# PRO30.net
KiCad netlist of a schematic drawn in EAGLE
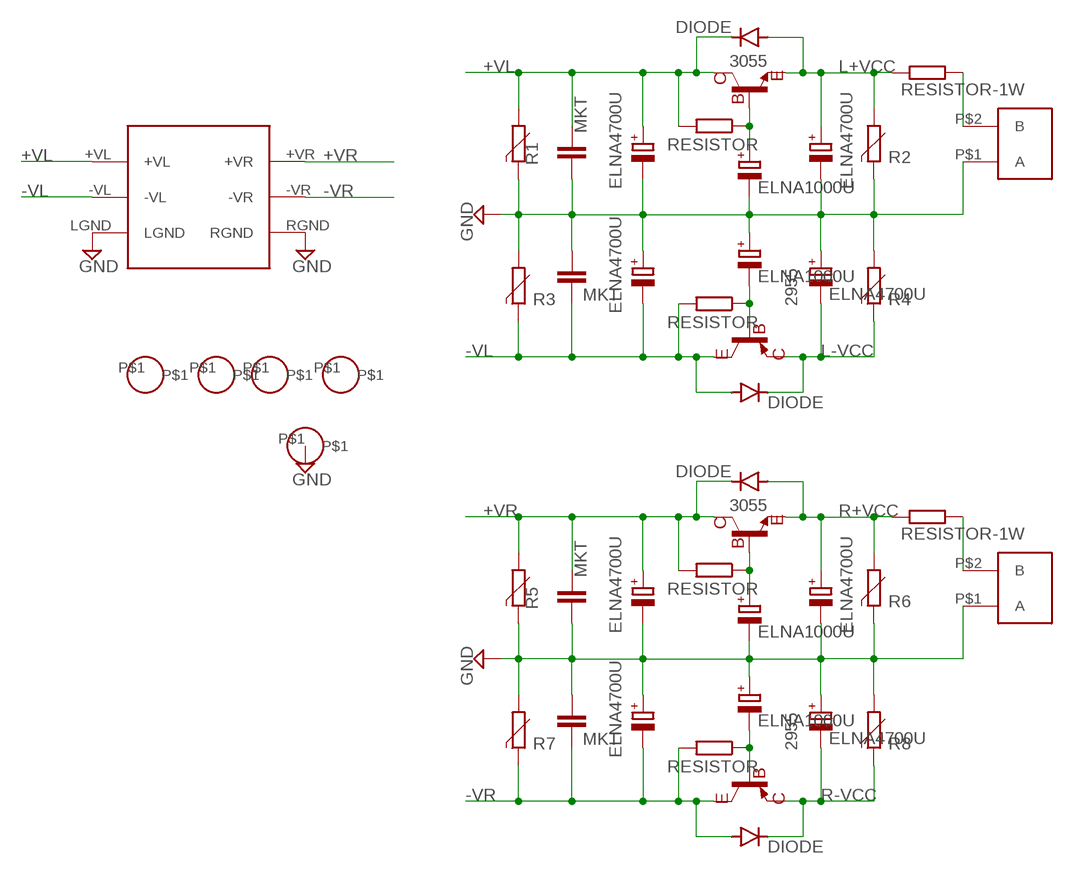
[diagram p0: schematic, sheet 1]
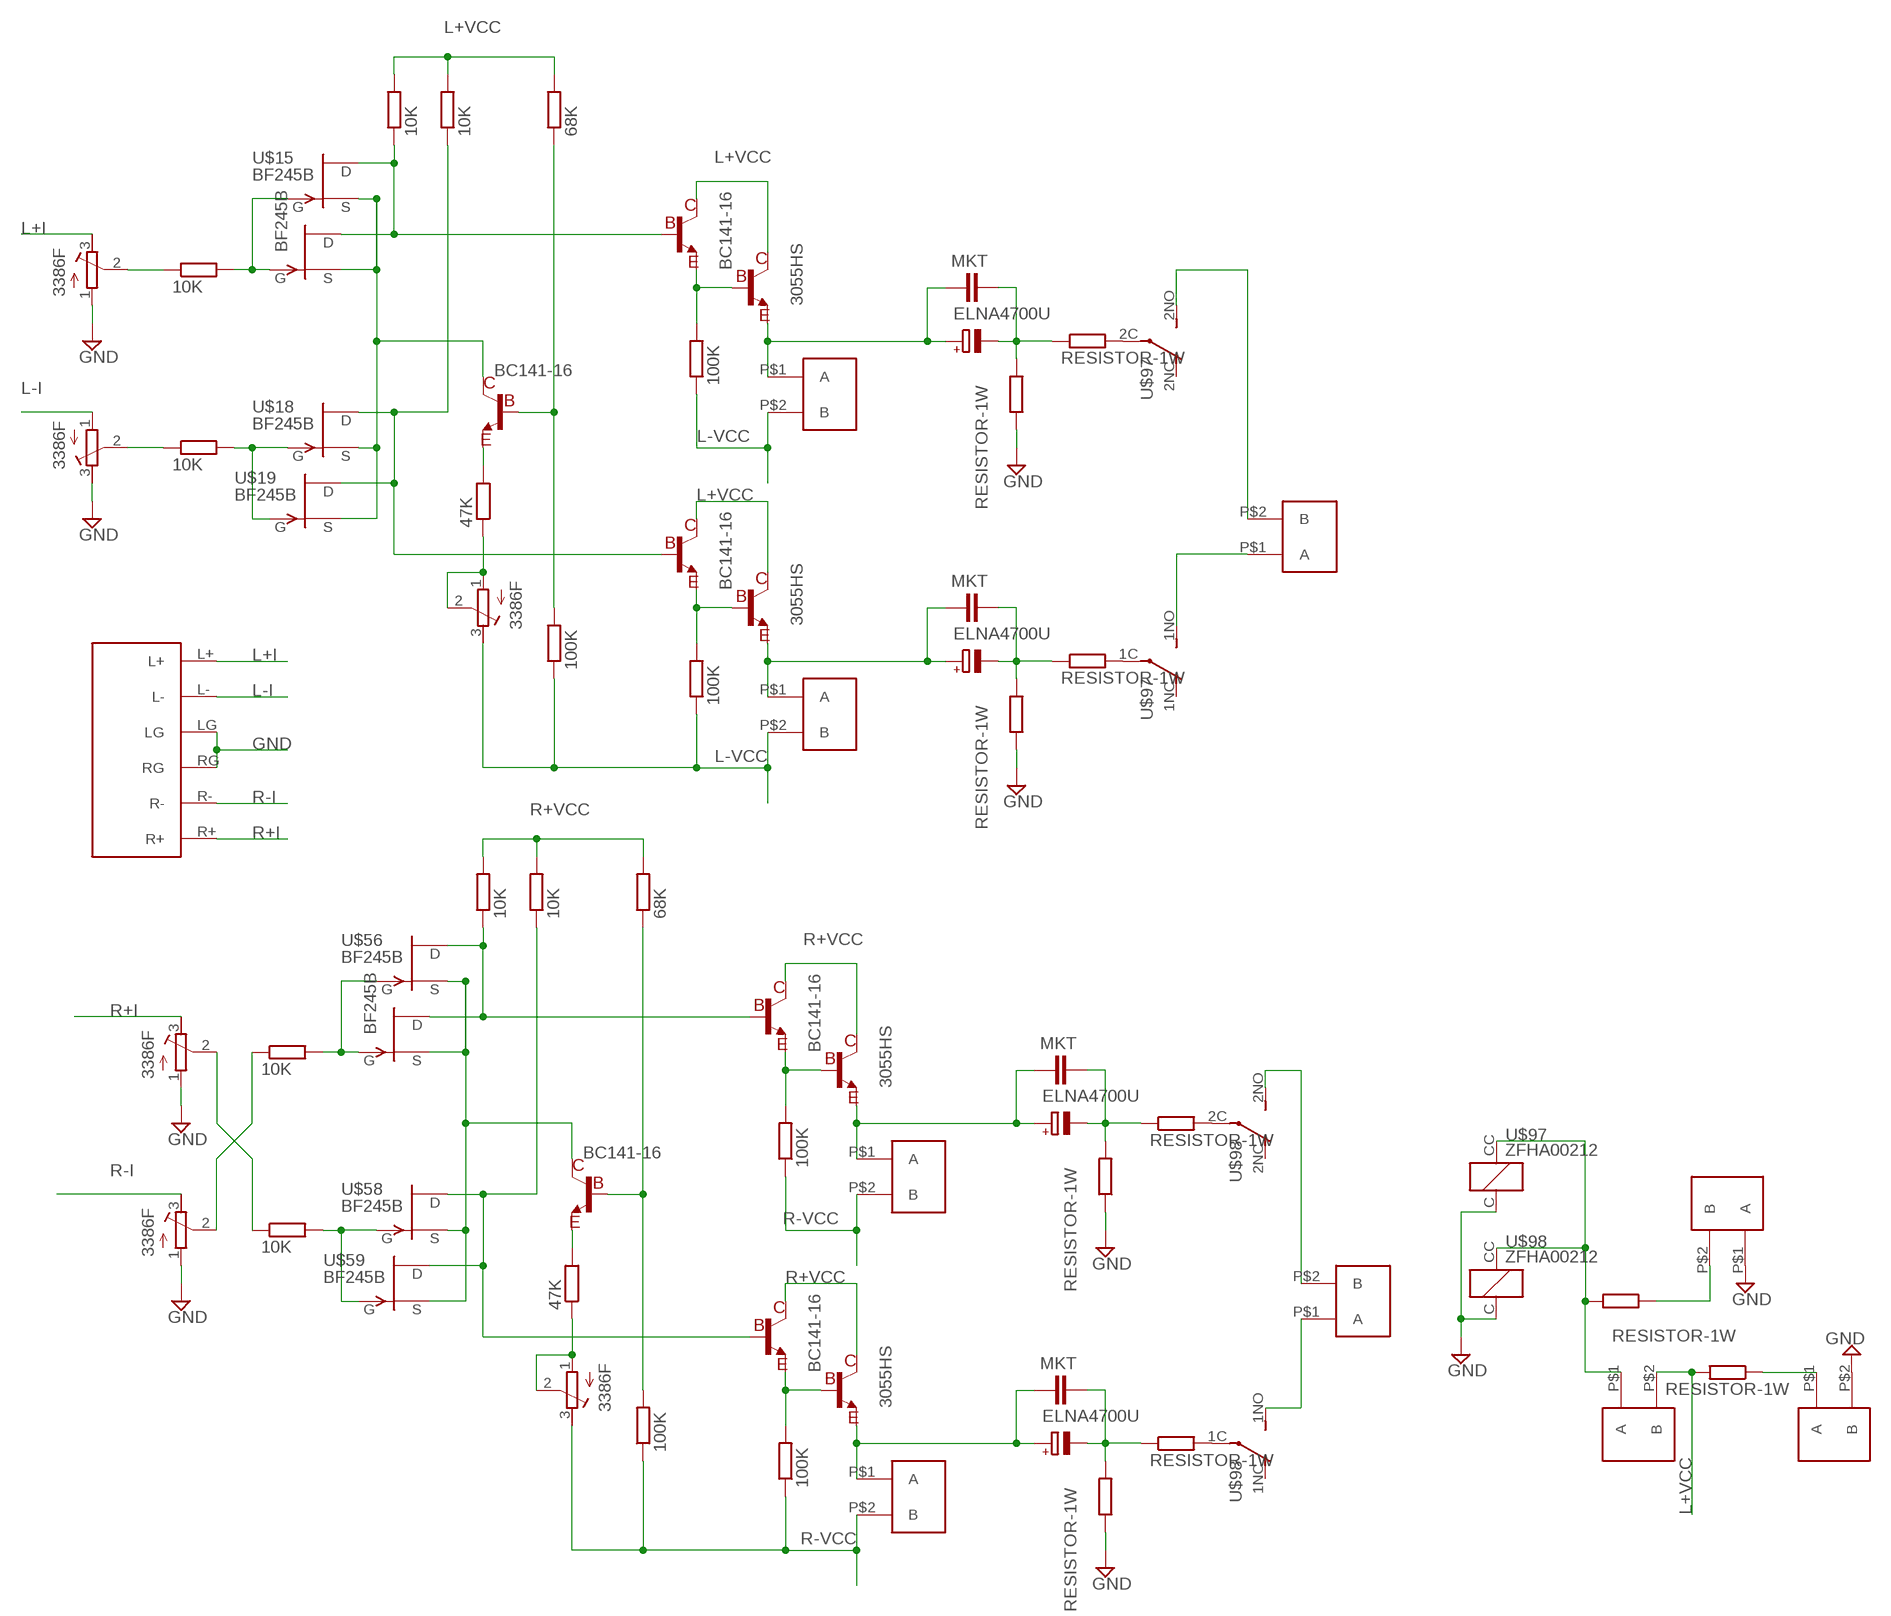
[diagram p1: schematic, sheet 2]

(export (version "E")
  (design (tool "Eeschema 10.0.6"))
  (components
    (comp (ref "DN>L")
      (value "OUT2")
      (footprint "eagle-import:OUT2_")
      (libsource (lib "eagle-import") (part "OUT2"))
    )
    (comp (ref "DP_SW")
      (value "OUT2")
      (footprint "eagle-import:OUT2_")
      (libsource (lib "eagle-import") (part "OUT2"))
    )
    (comp (ref "U$2")
      (value "AUDIO_INPUT")
      (footprint "eagle-import:AUDIO_INPUT")
      (libsource (lib "eagle-import") (part "AUDIO_INPUT"))
    )
    (comp (ref "U$4")
      (value "3386F")
      (footprint "eagle-import:3386")
      (libsource (lib "eagle-import") (part "3386F"))
    )
    (comp (ref "U$8")
      (value "3386F")
      (footprint "eagle-import:3386")
      (libsource (lib "eagle-import") (part "3386F"))
    )
    (comp (ref "U$11")
      (value "10K")
      (footprint "eagle-import:RESISTOR")
      (libsource (lib "eagle-import") (part "RESISTOR"))
    )
    (comp (ref "U$13")
      (value "68K")
      (footprint "eagle-import:RESISTOR")
      (libsource (lib "eagle-import") (part "RESISTOR"))
    )
    (comp (ref "U$14")
      (value "BC141-16")
      (footprint "eagle-import:TO39")
      (libsource (lib "eagle-import") (part "BC141-16"))
    )
    (comp (ref "U$15")
      (value "BF245B")
      (footprint "eagle-import:TO39")
      (libsource (lib "eagle-import") (part "BF245B"))
    )
    (comp (ref "U$17")
      (value "BF245B")
      (footprint "eagle-import:TO39")
      (libsource (lib "eagle-import") (part "BF245B"))
    )
    (comp (ref "U$18")
      (value "BF245B")
      (footprint "eagle-import:TO39")
      (libsource (lib "eagle-import") (part "BF245B"))
    )
    (comp (ref "U$19")
      (value "BF245B")
      (footprint "eagle-import:TO39")
      (libsource (lib "eagle-import") (part "BF245B"))
    )
    (comp (ref "U$20")
      (value "10K")
      (footprint "eagle-import:RESISTOR")
      (libsource (lib "eagle-import") (part "RESISTOR"))
    )
    (comp (ref "U$21")
      (value "10K")
      (footprint "eagle-import:RESISTOR")
      (libsource (lib "eagle-import") (part "RESISTOR"))
    )
    (comp (ref "U$22")
      (value "BC141-16")
      (footprint "eagle-import:TO39")
      (libsource (lib "eagle-import") (part "BC141-16"))
    )
    (comp (ref "U$23")
      (value "BC141-16")
      (footprint "eagle-import:TO39")
      (libsource (lib "eagle-import") (part "BC141-16"))
    )
    (comp (ref "U$25")
      (value "10K")
      (footprint "eagle-import:RESISTOR")
      (libsource (lib "eagle-import") (part "RESISTOR"))
    )
    (comp (ref "U$27")
      (value "47K")
      (footprint "eagle-import:RESISTOR")
      (libsource (lib "eagle-import") (part "RESISTOR"))
    )
    (comp (ref "U$31")
      (value "3386F")
      (footprint "eagle-import:3386")
      (libsource (lib "eagle-import") (part "3386F"))
    )
    (comp (ref "U$32")
      (value "3055HS")
      (footprint "eagle-import:POWER_TRANS_WHS")
      (libsource (lib "eagle-import") (part "3055HS"))
    )
    (comp (ref "U$33")
      (value "3055HS")
      (footprint "eagle-import:POWER_TRANS_WHS")
      (libsource (lib "eagle-import") (part "3055HS"))
    )
    (comp (ref "U$35")
      (value "OUT3")
      (footprint "eagle-import:OUT3_")
      (libsource (lib "eagle-import") (part "OUT3"))
    )
    (comp (ref "U$36")
      (value "ELNA4700U")
      (footprint "eagle-import:4700U")
      (libsource (lib "eagle-import") (part "ELNA4700U"))
    )
    (comp (ref "U$37")
      (value "MKT")
      (footprint "eagle-import:NTC")
      (libsource (lib "eagle-import") (part "MKT"))
    )
    (comp (ref "U$38")
      (value "RESISTOR-1W")
      (footprint "eagle-import:RESISTOR-1W")
      (libsource (lib "eagle-import") (part "RESISTOR-1W"))
    )
    (comp (ref "U$39")
      (value "RESISTOR-1W")
      (footprint "eagle-import:RESISTOR-1W")
      (libsource (lib "eagle-import") (part "RESISTOR-1W"))
    )
    (comp (ref "U$44")
      (value "OUT3")
      (footprint "eagle-import:OUT3_")
      (libsource (lib "eagle-import") (part "OUT3"))
    )
    (comp (ref "U$45")
      (value "ELNA4700U")
      (footprint "eagle-import:4700U")
      (libsource (lib "eagle-import") (part "ELNA4700U"))
    )
    (comp (ref "U$46")
      (value "MKT")
      (footprint "eagle-import:NTC")
      (libsource (lib "eagle-import") (part "MKT"))
    )
    (comp (ref "U$47")
      (value "RESISTOR-1W")
      (footprint "eagle-import:RESISTOR-1W")
      (libsource (lib "eagle-import") (part "RESISTOR-1W"))
    )
    (comp (ref "U$48")
      (value "RESISTOR-1W")
      (footprint "eagle-import:RESISTOR-1W")
      (libsource (lib "eagle-import") (part "RESISTOR-1W"))
    )
    (comp (ref "U$49")
      (value "100K")
      (footprint "eagle-import:RESISTOR")
      (libsource (lib "eagle-import") (part "RESISTOR"))
    )
    (comp (ref "U$50")
      (value "100K")
      (footprint "eagle-import:RESISTOR")
      (libsource (lib "eagle-import") (part "RESISTOR"))
    )
    (comp (ref "U$51")
      (value "100K")
      (footprint "eagle-import:RESISTOR")
      (libsource (lib "eagle-import") (part "RESISTOR"))
    )
    (comp (ref "U$52")
      (value "3386F")
      (footprint "eagle-import:3386")
      (libsource (lib "eagle-import") (part "3386F"))
    )
    (comp (ref "U$53")
      (value "3386F")
      (footprint "eagle-import:3386")
      (libsource (lib "eagle-import") (part "3386F"))
    )
    (comp (ref "U$54")
      (value "10K")
      (footprint "eagle-import:RESISTOR")
      (libsource (lib "eagle-import") (part "RESISTOR"))
    )
    (comp (ref "U$55")
      (value "BC141-16")
      (footprint "eagle-import:TO39")
      (libsource (lib "eagle-import") (part "BC141-16"))
    )
    (comp (ref "U$56")
      (value "BF245B")
      (footprint "eagle-import:TO39")
      (libsource (lib "eagle-import") (part "BF245B"))
    )
    (comp (ref "U$57")
      (value "BF245B")
      (footprint "eagle-import:TO39")
      (libsource (lib "eagle-import") (part "BF245B"))
    )
    (comp (ref "U$58")
      (value "BF245B")
      (footprint "eagle-import:TO39")
      (libsource (lib "eagle-import") (part "BF245B"))
    )
    (comp (ref "U$59")
      (value "BF245B")
      (footprint "eagle-import:TO39")
      (libsource (lib "eagle-import") (part "BF245B"))
    )
    (comp (ref "U$60")
      (value "10K")
      (footprint "eagle-import:RESISTOR")
      (libsource (lib "eagle-import") (part "RESISTOR"))
    )
    (comp (ref "U$61")
      (value "BC141-16")
      (footprint "eagle-import:TO39")
      (libsource (lib "eagle-import") (part "BC141-16"))
    )
    (comp (ref "U$62")
      (value "47K")
      (footprint "eagle-import:RESISTOR")
      (libsource (lib "eagle-import") (part "RESISTOR"))
    )
    (comp (ref "U$63")
      (value "3386F")
      (footprint "eagle-import:3386")
      (libsource (lib "eagle-import") (part "3386F"))
    )
    (comp (ref "U$64")
      (value "3055HS")
      (footprint "eagle-import:POWER_TRANS_WHS")
      (libsource (lib "eagle-import") (part "3055HS"))
    )
    (comp (ref "U$65")
      (value "OUT3")
      (footprint "eagle-import:OUT3_")
      (libsource (lib "eagle-import") (part "OUT3"))
    )
    (comp (ref "U$66")
      (value "ELNA4700U")
      (footprint "eagle-import:4700U")
      (libsource (lib "eagle-import") (part "ELNA4700U"))
    )
    (comp (ref "U$67")
      (value "MKT")
      (footprint "eagle-import:NTC")
      (libsource (lib "eagle-import") (part "MKT"))
    )
    (comp (ref "U$68")
      (value "RESISTOR-1W")
      (footprint "eagle-import:RESISTOR-1W")
      (libsource (lib "eagle-import") (part "RESISTOR-1W"))
    )
    (comp (ref "U$69")
      (value "RESISTOR-1W")
      (footprint "eagle-import:RESISTOR-1W")
      (libsource (lib "eagle-import") (part "RESISTOR-1W"))
    )
    (comp (ref "U$70")
      (value "BC141-16")
      (footprint "eagle-import:TO39")
      (libsource (lib "eagle-import") (part "BC141-16"))
    )
    (comp (ref "U$71")
      (value "3055HS")
      (footprint "eagle-import:POWER_TRANS_WHS")
      (libsource (lib "eagle-import") (part "3055HS"))
    )
    (comp (ref "U$72")
      (value "OUT3")
      (footprint "eagle-import:OUT3_")
      (libsource (lib "eagle-import") (part "OUT3"))
    )
    (comp (ref "U$73")
      (value "ELNA4700U")
      (footprint "eagle-import:4700U")
      (libsource (lib "eagle-import") (part "ELNA4700U"))
    )
    (comp (ref "U$74")
      (value "MKT")
      (footprint "eagle-import:NTC")
      (libsource (lib "eagle-import") (part "MKT"))
    )
    (comp (ref "U$75")
      (value "RESISTOR-1W")
      (footprint "eagle-import:RESISTOR-1W")
      (libsource (lib "eagle-import") (part "RESISTOR-1W"))
    )
    (comp (ref "U$76")
      (value "RESISTOR-1W")
      (footprint "eagle-import:RESISTOR-1W")
      (libsource (lib "eagle-import") (part "RESISTOR-1W"))
    )
    (comp (ref "U$77")
      (value "100K")
      (footprint "eagle-import:RESISTOR")
      (libsource (lib "eagle-import") (part "RESISTOR"))
    )
    (comp (ref "U$78")
      (value "100K")
      (footprint "eagle-import:RESISTOR")
      (libsource (lib "eagle-import") (part "RESISTOR"))
    )
    (comp (ref "U$79")
      (value "100K")
      (footprint "eagle-import:RESISTOR")
      (libsource (lib "eagle-import") (part "RESISTOR"))
    )
    (comp (ref "U$80")
      (value "68K")
      (footprint "eagle-import:RESISTOR")
      (libsource (lib "eagle-import") (part "RESISTOR"))
    )
    (comp (ref "U$81")
      (value "10K")
      (footprint "eagle-import:RESISTOR")
      (libsource (lib "eagle-import") (part "RESISTOR"))
    )
    (comp (ref "U$82")
      (value "10K")
      (footprint "eagle-import:RESISTOR")
      (libsource (lib "eagle-import") (part "RESISTOR"))
    )
    (comp (ref "U$97")
      (value "ZFHA00212")
      (footprint "eagle-import:ZFHA002")
      (libsource (lib "eagle-import") (part "ZFHA00212"))
    )
    (comp (ref "U$98")
      (value "ZFHA00212")
      (footprint "eagle-import:ZFHA002")
      (libsource (lib "eagle-import") (part "ZFHA00212"))
    )
    (comp (ref "U$99")
      (value "RESISTOR-1W")
      (footprint "eagle-import:RESISTOR-1W")
      (libsource (lib "eagle-import") (part "RESISTOR-1W"))
    )
    (comp (ref "U$100")
      (value "RESISTOR-1W")
      (footprint "eagle-import:RESISTOR-1W")
      (libsource (lib "eagle-import") (part "RESISTOR-1W"))
    )
    (comp (ref "U$103")
      (value "OUT2")
      (footprint "eagle-import:OUT2_")
      (libsource (lib "eagle-import") (part "OUT2"))
    )
    (comp (ref "U$104")
      (value "OUT3")
      (footprint "eagle-import:OUT3_")
      (libsource (lib "eagle-import") (part "OUT3"))
    )
    (comp (ref "U$105")
      (value "OUT3")
      (footprint "eagle-import:OUT3_")
      (libsource (lib "eagle-import") (part "OUT3"))
    )
    (comp (ref "R1")
      (value "NTC")
      (footprint "eagle-import:NTC")
      (libsource (lib "eagle-import") (part "NTC"))
    )
    (comp (ref "R2")
      (value "NTC")
      (footprint "eagle-import:NTC")
      (libsource (lib "eagle-import") (part "NTC"))
    )
    (comp (ref "R3")
      (value "NTC")
      (footprint "eagle-import:NTC")
      (libsource (lib "eagle-import") (part "NTC"))
    )
    (comp (ref "R4")
      (value "NTC")
      (footprint "eagle-import:NTC")
      (libsource (lib "eagle-import") (part "NTC"))
    )
    (comp (ref "R5")
      (value "NTC")
      (footprint "eagle-import:NTC")
      (libsource (lib "eagle-import") (part "NTC"))
    )
    (comp (ref "R6")
      (value "NTC")
      (footprint "eagle-import:NTC")
      (libsource (lib "eagle-import") (part "NTC"))
    )
    (comp (ref "R7")
      (value "NTC")
      (footprint "eagle-import:NTC")
      (libsource (lib "eagle-import") (part "NTC"))
    )
    (comp (ref "R8")
      (value "NTC")
      (footprint "eagle-import:NTC")
      (libsource (lib "eagle-import") (part "NTC"))
    )
    (comp (ref "U$1")
      (value "INPUT")
      (footprint "eagle-import:INPUT")
      (libsource (lib "eagle-import") (part "INPUT"))
    )
    (comp (ref "U$3")
      (value "ELNA4700U")
      (footprint "eagle-import:4700U")
      (libsource (lib "eagle-import") (part "ELNA4700U"))
    )
    (comp (ref "U$5")
      (value "ELNA4700U")
      (footprint "eagle-import:4700U")
      (libsource (lib "eagle-import") (part "ELNA4700U"))
    )
    (comp (ref "U$6")
      (value "ELNA4700U")
      (footprint "eagle-import:4700U")
      (libsource (lib "eagle-import") (part "ELNA4700U"))
    )
    (comp (ref "U$7")
      (value "ELNA4700U")
      (footprint "eagle-import:4700U")
      (libsource (lib "eagle-import") (part "ELNA4700U"))
    )
    (comp (ref "U$9")
      (value "ELNA4700U")
      (footprint "eagle-import:4700U")
      (libsource (lib "eagle-import") (part "ELNA4700U"))
    )
    (comp (ref "U$10")
      (value "ELNA4700U")
      (footprint "eagle-import:4700U")
      (libsource (lib "eagle-import") (part "ELNA4700U"))
    )
    (comp (ref "U$12")
      (value "ELNA1000U")
      (footprint "eagle-import:1000U")
      (libsource (lib "eagle-import") (part "ELNA1000U"))
    )
    (comp (ref "U$16")
      (value "ELNA1000U")
      (footprint "eagle-import:1000U")
      (libsource (lib "eagle-import") (part "ELNA1000U"))
    )
    (comp (ref "U$24")
      (value "2955")
      (footprint "eagle-import:POWER_TRANS")
      (libsource (lib "eagle-import") (part "2955"))
    )
    (comp (ref "U$26")
      (value "3055")
      (footprint "eagle-import:POWER_TRANS")
      (libsource (lib "eagle-import") (part "3055"))
    )
    (comp (ref "U$28")
      (value "DIODE")
      (footprint "eagle-import:DIODE")
      (libsource (lib "eagle-import") (part "DIODE"))
    )
    (comp (ref "U$29")
      (value "DIODE")
      (footprint "eagle-import:DIODE")
      (libsource (lib "eagle-import") (part "DIODE"))
    )
    (comp (ref "U$30")
      (value "MKT")
      (footprint "eagle-import:NTC")
      (libsource (lib "eagle-import") (part "MKT"))
    )
    (comp (ref "U$34")
      (value "MKT")
      (footprint "eagle-import:NTC")
      (libsource (lib "eagle-import") (part "MKT"))
    )
    (comp (ref "U$40")
      (value "RESISTOR")
      (footprint "eagle-import:RESISTOR")
      (libsource (lib "eagle-import") (part "RESISTOR"))
    )
    (comp (ref "U$41")
      (value "OUT2")
      (footprint "eagle-import:OUT2_")
      (libsource (lib "eagle-import") (part "OUT2"))
    )
    (comp (ref "U$42")
      (value "RESISTOR-1W")
      (footprint "eagle-import:RESISTOR-1W")
      (libsource (lib "eagle-import") (part "RESISTOR-1W"))
    )
    (comp (ref "U$43")
      (value "RESISTOR")
      (footprint "eagle-import:RESISTOR")
      (libsource (lib "eagle-import") (part "RESISTOR"))
    )
    (comp (ref "U$83")
      (value "ELNA4700U")
      (footprint "eagle-import:4700U")
      (libsource (lib "eagle-import") (part "ELNA4700U"))
    )
    (comp (ref "U$84")
      (value "ELNA4700U")
      (footprint "eagle-import:4700U")
      (libsource (lib "eagle-import") (part "ELNA4700U"))
    )
    (comp (ref "U$85")
      (value "ELNA1000U")
      (footprint "eagle-import:1000U")
      (libsource (lib "eagle-import") (part "ELNA1000U"))
    )
    (comp (ref "U$86")
      (value "ELNA1000U")
      (footprint "eagle-import:1000U")
      (libsource (lib "eagle-import") (part "ELNA1000U"))
    )
    (comp (ref "U$87")
      (value "2955")
      (footprint "eagle-import:POWER_TRANS")
      (libsource (lib "eagle-import") (part "2955"))
    )
    (comp (ref "U$88")
      (value "3055")
      (footprint "eagle-import:POWER_TRANS")
      (libsource (lib "eagle-import") (part "3055"))
    )
    (comp (ref "U$89")
      (value "DIODE")
      (footprint "eagle-import:DIODE")
      (libsource (lib "eagle-import") (part "DIODE"))
    )
    (comp (ref "U$90")
      (value "DIODE")
      (footprint "eagle-import:DIODE")
      (libsource (lib "eagle-import") (part "DIODE"))
    )
    (comp (ref "U$91")
      (value "MKT")
      (footprint "eagle-import:NTC")
      (libsource (lib "eagle-import") (part "MKT"))
    )
    (comp (ref "U$92")
      (value "MKT")
      (footprint "eagle-import:NTC")
      (libsource (lib "eagle-import") (part "MKT"))
    )
    (comp (ref "U$93")
      (value "RESISTOR")
      (footprint "eagle-import:RESISTOR")
      (libsource (lib "eagle-import") (part "RESISTOR"))
    )
    (comp (ref "U$94")
      (value "OUT2")
      (footprint "eagle-import:OUT2_")
      (libsource (lib "eagle-import") (part "OUT2"))
    )
    (comp (ref "U$95")
      (value "RESISTOR-1W")
      (footprint "eagle-import:RESISTOR-1W")
      (libsource (lib "eagle-import") (part "RESISTOR-1W"))
    )
    (comp (ref "U$96")
      (value "RESISTOR")
      (footprint "eagle-import:RESISTOR")
      (libsource (lib "eagle-import") (part "RESISTOR"))
    )
    (comp (ref "U$101")
      (value "HOLE")
      (footprint "eagle-import:HOLE")
      (libsource (lib "eagle-import") (part "HOLE"))
    )
    (comp (ref "U$102")
      (value "HOLE")
      (footprint "eagle-import:HOLE")
      (libsource (lib "eagle-import") (part "HOLE"))
    )
    (comp (ref "U$106")
      (value "HOLE")
      (footprint "eagle-import:HOLE")
      (libsource (lib "eagle-import") (part "HOLE"))
    )
    (comp (ref "U$107")
      (value "HOLE")
      (footprint "eagle-import:HOLE")
      (libsource (lib "eagle-import") (part "HOLE"))
    )
    (comp (ref "U$108")
      (value "HOLE")
      (footprint "eagle-import:HOLE")
      (libsource (lib "eagle-import") (part "HOLE"))
    )
  )
  (nets
    (net (code "1") (name "+VL") (class "Default")
      (node (ref "R1") (pin "2") (pinfunction "2_2") (pintype "passive"))
      (node (ref "U$1") (pin "+VL") (pinfunction "+VL_+VL") (pintype "bidirectional"))
      (node (ref "U$26") (pin "C") (pinfunction "C_C") (pintype "passive"))
      (node (ref "U$28") (pin "C") (pinfunction "C_C") (pintype "passive"))
      (node (ref "U$3") (pin "+") (pinfunction "+_+") (pintype "passive"))
      (node (ref "U$30") (pin "1") (pinfunction "1_1") (pintype "passive"))
      (node (ref "U$40") (pin "P$2") (pinfunction "2_P$2") (pintype "passive"))
    )
    (net (code "2") (name "+VR") (class "Default")
      (node (ref "R5") (pin "2") (pinfunction "2_2") (pintype "passive"))
      (node (ref "U$1") (pin "+VR") (pinfunction "+VR_+VR") (pintype "bidirectional"))
      (node (ref "U$88") (pin "C") (pinfunction "C_C") (pintype "passive"))
      (node (ref "U$89") (pin "C") (pinfunction "C_C") (pintype "passive"))
      (node (ref "U$9") (pin "+") (pinfunction "+_+") (pintype "passive"))
      (node (ref "U$91") (pin "1") (pinfunction "1_1") (pintype "passive"))
      (node (ref "U$93") (pin "P$2") (pinfunction "2_P$2") (pintype "passive"))
    )
    (net (code "3") (name "-VL") (class "Default")
      (node (ref "R3") (pin "1") (pinfunction "1_1") (pintype "passive"))
      (node (ref "U$1") (pin "-VL") (pinfunction "-VL_-VL") (pintype "bidirectional"))
      (node (ref "U$24") (pin "C") (pinfunction "C_C") (pintype "passive"))
      (node (ref "U$29") (pin "A") (pinfunction "A_A") (pintype "passive"))
      (node (ref "U$34") (pin "2") (pinfunction "2_2") (pintype "passive"))
      (node (ref "U$43") (pin "P$2") (pinfunction "2_P$2") (pintype "passive"))
      (node (ref "U$7") (pin "-") (pinfunction "-_-") (pintype "passive"))
    )
    (net (code "4") (name "-VR") (class "Default")
      (node (ref "R7") (pin "1") (pinfunction "1_1") (pintype "passive"))
      (node (ref "U$1") (pin "-VR") (pinfunction "-VR_-VR") (pintype "bidirectional"))
      (node (ref "U$84") (pin "-") (pinfunction "-_-") (pintype "passive"))
      (node (ref "U$87") (pin "C") (pinfunction "C_C") (pintype "passive"))
      (node (ref "U$90") (pin "A") (pinfunction "A_A") (pintype "passive"))
      (node (ref "U$92") (pin "2") (pinfunction "2_2") (pintype "passive"))
      (node (ref "U$96") (pin "P$2") (pinfunction "2_P$2") (pintype "passive"))
    )
    (net (code "5") (name "GND") (class "Default")
      (node (ref "DN>L") (pin "P$2") (pinfunction "B_P$2") (pintype "bidirectional"))
      (node (ref "R1") (pin "1") (pinfunction "1_1") (pintype "passive"))
      (node (ref "R2") (pin "1") (pinfunction "1_1") (pintype "passive"))
      (node (ref "R3") (pin "2") (pinfunction "2_2") (pintype "passive"))
      (node (ref "R4") (pin "2") (pinfunction "2_2") (pintype "passive"))
      (node (ref "R5") (pin "1") (pinfunction "1_1") (pintype "passive"))
      (node (ref "R6") (pin "1") (pinfunction "1_1") (pintype "passive"))
      (node (ref "R7") (pin "2") (pinfunction "2_2") (pintype "passive"))
      (node (ref "R8") (pin "2") (pinfunction "2_2") (pintype "passive"))
      (node (ref "U$1") (pin "LGND") (pinfunction "LGND_LGND") (pintype "bidirectional"))
      (node (ref "U$1") (pin "RGND") (pinfunction "RGND_RGND") (pintype "bidirectional"))
      (node (ref "U$10") (pin "+") (pinfunction "+_+") (pintype "passive"))
      (node (ref "U$103") (pin "P$1") (pinfunction "A_P$1") (pintype "bidirectional"))
      (node (ref "U$108") (pin "P$1") (pinfunction "P$1_P$1") (pintype "bidirectional"))
      (node (ref "U$12") (pin "-") (pinfunction "-_-") (pintype "passive"))
      (node (ref "U$16") (pin "+") (pinfunction "+_+") (pintype "passive"))
      (node (ref "U$2") (pin "LG") (pinfunction "LG_LG") (pintype "bidirectional"))
      (node (ref "U$2") (pin "RG") (pinfunction "RG_RG") (pintype "bidirectional"))
      (node (ref "U$3") (pin "-") (pinfunction "-_-") (pintype "passive"))
      (node (ref "U$30") (pin "2") (pinfunction "2_2") (pintype "passive"))
      (node (ref "U$34") (pin "1") (pinfunction "1_1") (pintype "passive"))
      (node (ref "U$38") (pin "P$1") (pinfunction "1_P$1") (pintype "passive"))
      (node (ref "U$4") (pin "1") (pinfunction "1_1") (pintype "passive"))
      (node (ref "U$41") (pin "P$1") (pinfunction "A_P$1") (pintype "bidirectional"))
      (node (ref "U$47") (pin "P$1") (pinfunction "1_P$1") (pintype "passive"))
      (node (ref "U$5") (pin "+") (pinfunction "+_+") (pintype "passive"))
      (node (ref "U$52") (pin "1") (pinfunction "1_1") (pintype "passive"))
      (node (ref "U$53") (pin "1") (pinfunction "1_1") (pintype "passive"))
      (node (ref "U$6") (pin "-") (pinfunction "-_-") (pintype "passive"))
      (node (ref "U$68") (pin "P$1") (pinfunction "1_P$1") (pintype "passive"))
      (node (ref "U$7") (pin "+") (pinfunction "+_+") (pintype "passive"))
      (node (ref "U$75") (pin "P$1") (pinfunction "1_P$1") (pintype "passive"))
      (node (ref "U$8") (pin "3") (pinfunction "3_3") (pintype "passive"))
      (node (ref "U$83") (pin "-") (pinfunction "-_-") (pintype "passive"))
      (node (ref "U$84") (pin "+") (pinfunction "+_+") (pintype "passive"))
      (node (ref "U$85") (pin "-") (pinfunction "-_-") (pintype "passive"))
      (node (ref "U$86") (pin "+") (pinfunction "+_+") (pintype "passive"))
      (node (ref "U$9") (pin "-") (pinfunction "-_-") (pintype "passive"))
      (node (ref "U$91") (pin "2") (pinfunction "2_2") (pintype "passive"))
      (node (ref "U$92") (pin "1") (pinfunction "1_1") (pintype "passive"))
      (node (ref "U$94") (pin "P$1") (pinfunction "A_P$1") (pintype "bidirectional"))
      (node (ref "U$97") (pin "C") (pinfunction "C_C") (pintype "passive"))
      (node (ref "U$98") (pin "C") (pinfunction "C_C") (pintype "passive"))
    )
    (net (code "6") (name "L+I") (class "Default")
      (node (ref "U$2") (pin "L+") (pinfunction "L+_L+") (pintype "bidirectional"))
      (node (ref "U$4") (pin "3") (pinfunction "3_3") (pintype "passive"))
    )
    (net (code "7") (name "L+VCC") (class "Default")
      (node (ref "DP_SW") (pin "P$2") (pinfunction "B_P$2") (pintype "bidirectional"))
      (node (ref "R2") (pin "2") (pinfunction "2_2") (pintype "passive"))
      (node (ref "U$13") (pin "P$2") (pinfunction "2_P$2") (pintype "passive"))
      (node (ref "U$20") (pin "P$2") (pinfunction "2_P$2") (pintype "passive"))
      (node (ref "U$22") (pin "C/G") (pinfunction "C_C/G") (pintype "passive"))
      (node (ref "U$23") (pin "C/G") (pinfunction "C_C/G") (pintype "passive"))
      (node (ref "U$25") (pin "P$2") (pinfunction "2_P$2") (pintype "passive"))
      (node (ref "U$26") (pin "E") (pinfunction "E_E") (pintype "passive"))
      (node (ref "U$28") (pin "A") (pinfunction "A_A") (pintype "passive"))
      (node (ref "U$32") (pin "C") (pinfunction "C_C") (pintype "passive"))
      (node (ref "U$33") (pin "C") (pinfunction "C_C") (pintype "passive"))
      (node (ref "U$42") (pin "P$1") (pinfunction "1_P$1") (pintype "passive"))
      (node (ref "U$6") (pin "+") (pinfunction "+_+") (pintype "passive"))
      (node (ref "U$99") (pin "P$2") (pinfunction "2_P$2") (pintype "passive"))
    )
    (net (code "8") (name "L-I") (class "Default")
      (node (ref "U$2") (pin "L-") (pinfunction "L-_L-") (pintype "bidirectional"))
      (node (ref "U$8") (pin "1") (pinfunction "1_1") (pintype "passive"))
    )
    (net (code "9") (name "L-VCC") (class "Default")
      (node (ref "R4") (pin "1") (pinfunction "1_1") (pintype "passive"))
      (node (ref "U$24") (pin "E") (pinfunction "E_E") (pintype "passive"))
      (node (ref "U$29") (pin "C") (pinfunction "C_C") (pintype "passive"))
      (node (ref "U$31") (pin "3") (pinfunction "3_3") (pintype "passive"))
      (node (ref "U$35") (pin "P$2") (pinfunction "B_P$2") (pintype "bidirectional"))
      (node (ref "U$44") (pin "P$2") (pinfunction "B_P$2") (pintype "bidirectional"))
      (node (ref "U$49") (pin "P$1") (pinfunction "1_P$1") (pintype "passive"))
      (node (ref "U$5") (pin "-") (pinfunction "-_-") (pintype "passive"))
      (node (ref "U$50") (pin "P$1") (pinfunction "1_P$1") (pintype "passive"))
      (node (ref "U$51") (pin "P$1") (pinfunction "1_P$1") (pintype "passive"))
    )
    (net (code "10") (name "Net-(DN>L-A)") (class "Default")
      (node (ref "DN>L") (pin "P$1") (pinfunction "A_P$1") (pintype "bidirectional"))
      (node (ref "U$99") (pin "P$1") (pinfunction "1_P$1") (pintype "passive"))
    )
    (net (code "11") (name "Net-(DP_SW-A)") (class "Default")
      (node (ref "DP_SW") (pin "P$1") (pinfunction "A_P$1") (pintype "bidirectional"))
      (node (ref "U$100") (pin "P$2") (pinfunction "2_P$2") (pintype "passive"))
      (node (ref "U$97") (pin "CC") (pinfunction "CT_CC") (pintype "passive"))
      (node (ref "U$98") (pin "CC") (pinfunction "CT_CC") (pintype "passive"))
    )
    (net (code "12") (name "Net-(U$11-1)") (class "Default")
      (node (ref "U$11") (pin "P$1") (pinfunction "1_P$1") (pintype "passive"))
      (node (ref "U$4") (pin "2") (pinfunction "2_2") (pintype "passive"))
    )
    (net (code "13") (name "Net-(U$11-2)") (class "Default")
      (node (ref "U$11") (pin "P$2") (pinfunction "2_P$2") (pintype "passive"))
      (node (ref "U$15") (pin "C/G") (pinfunction "G_C/G") (pintype "passive"))
      (node (ref "U$17") (pin "C/G") (pinfunction "G_C/G") (pintype "passive"))
    )
    (net (code "14") (name "Net-(U$13-1)") (class "Default")
      (node (ref "U$13") (pin "P$1") (pinfunction "1_P$1") (pintype "passive"))
      (node (ref "U$14") (pin "B/S") (pinfunction "B_B/S") (pintype "passive"))
      (node (ref "U$49") (pin "P$2") (pinfunction "2_P$2") (pintype "passive"))
    )
    (net (code "15") (name "Net-(U$14-C)") (class "Default")
      (node (ref "U$14") (pin "C/G") (pinfunction "C_C/G") (pintype "passive"))
      (node (ref "U$15") (pin "B/S") (pinfunction "S_B/S") (pintype "passive"))
      (node (ref "U$17") (pin "B/S") (pinfunction "S_B/S") (pintype "passive"))
      (node (ref "U$18") (pin "B/S") (pinfunction "S_B/S") (pintype "passive"))
      (node (ref "U$19") (pin "B/S") (pinfunction "S_B/S") (pintype "passive"))
    )
    (net (code "16") (name "Net-(U$14-E)") (class "Default")
      (node (ref "U$14") (pin "E/D") (pinfunction "E_E/D") (pintype "passive"))
      (node (ref "U$27") (pin "P$2") (pinfunction "2_P$2") (pintype "passive"))
    )
    (net (code "17") (name "Net-(U$15-D)") (class "Default")
      (node (ref "U$15") (pin "E/D") (pinfunction "D_E/D") (pintype "passive"))
      (node (ref "U$17") (pin "E/D") (pinfunction "D_E/D") (pintype "passive"))
      (node (ref "U$22") (pin "B/S") (pinfunction "B_B/S") (pintype "passive"))
      (node (ref "U$25") (pin "P$1") (pinfunction "1_P$1") (pintype "passive"))
    )
    (net (code "18") (name "Net-(U$18-D)") (class "Default")
      (node (ref "U$18") (pin "E/D") (pinfunction "D_E/D") (pintype "passive"))
      (node (ref "U$19") (pin "E/D") (pinfunction "D_E/D") (pintype "passive"))
      (node (ref "U$20") (pin "P$1") (pinfunction "1_P$1") (pintype "passive"))
      (node (ref "U$23") (pin "B/S") (pinfunction "B_B/S") (pintype "passive"))
    )
    (net (code "19") (name "Net-(U$18-G)") (class "Default")
      (node (ref "U$18") (pin "C/G") (pinfunction "G_C/G") (pintype "passive"))
      (node (ref "U$19") (pin "C/G") (pinfunction "G_C/G") (pintype "passive"))
      (node (ref "U$21") (pin "P$2") (pinfunction "2_P$2") (pintype "passive"))
    )
    (net (code "20") (name "Net-(U$21-1)") (class "Default")
      (node (ref "U$21") (pin "P$1") (pinfunction "1_P$1") (pintype "passive"))
      (node (ref "U$8") (pin "2") (pinfunction "2_2") (pintype "passive"))
    )
    (net (code "21") (name "Net-(U$22-E)") (class "Default")
      (node (ref "U$22") (pin "E/D") (pinfunction "E_E/D") (pintype "passive"))
      (node (ref "U$33") (pin "B") (pinfunction "B_B") (pintype "passive"))
      (node (ref "U$51") (pin "P$2") (pinfunction "2_P$2") (pintype "passive"))
    )
    (net (code "22") (name "Net-(U$23-E)") (class "Default")
      (node (ref "U$23") (pin "E/D") (pinfunction "E_E/D") (pintype "passive"))
      (node (ref "U$32") (pin "B") (pinfunction "B_B") (pintype "passive"))
      (node (ref "U$50") (pin "P$2") (pinfunction "2_P$2") (pintype "passive"))
    )
    (net (code "23") (name "Net-(U$27-1)") (class "Default")
      (node (ref "U$27") (pin "P$1") (pinfunction "1_P$1") (pintype "passive"))
      (node (ref "U$31") (pin "1") (pinfunction "1_1") (pintype "passive"))
      (node (ref "U$31") (pin "2") (pinfunction "2_2") (pintype "passive"))
    )
    (net (code "24") (name "Net-(U$35-A)") (class "Default")
      (node (ref "U$33") (pin "E") (pinfunction "E_E") (pintype "passive"))
      (node (ref "U$35") (pin "P$1") (pinfunction "A_P$1") (pintype "bidirectional"))
      (node (ref "U$36") (pin "+") (pinfunction "+_+") (pintype "passive"))
      (node (ref "U$37") (pin "1") (pinfunction "1_1") (pintype "passive"))
    )
    (net (code "25") (name "Net-(U$38-2)") (class "Default")
      (node (ref "U$36") (pin "-") (pinfunction "-_-") (pintype "passive"))
      (node (ref "U$37") (pin "2") (pinfunction "2_2") (pintype "passive"))
      (node (ref "U$38") (pin "P$2") (pinfunction "2_P$2") (pintype "passive"))
      (node (ref "U$39") (pin "P$1") (pinfunction "1_P$1") (pintype "passive"))
    )
    (net (code "26") (name "Net-(U$39-2)") (class "Default")
      (node (ref "U$39") (pin "P$2") (pinfunction "2_P$2") (pintype "passive"))
      (node (ref "U$97") (pin "2C") (pinfunction "C_2C") (pintype "passive"))
    )
    (net (code "27") (name "Net-(U$40-1)") (class "Default")
      (node (ref "U$12") (pin "+") (pinfunction "+_+") (pintype "passive"))
      (node (ref "U$26") (pin "B") (pinfunction "B_B") (pintype "passive"))
      (node (ref "U$40") (pin "P$1") (pinfunction "1_P$1") (pintype "passive"))
    )
    (net (code "28") (name "Net-(U$41-B)") (class "Default")
      (node (ref "U$41") (pin "P$2") (pinfunction "B_P$2") (pintype "bidirectional"))
      (node (ref "U$42") (pin "P$2") (pinfunction "2_P$2") (pintype "passive"))
    )
    (net (code "29") (name "Net-(U$43-1)") (class "Default")
      (node (ref "U$16") (pin "-") (pinfunction "-_-") (pintype "passive"))
      (node (ref "U$24") (pin "B") (pinfunction "B_B") (pintype "passive"))
      (node (ref "U$43") (pin "P$1") (pinfunction "1_P$1") (pintype "passive"))
    )
    (net (code "30") (name "Net-(U$44-A)") (class "Default")
      (node (ref "U$32") (pin "E") (pinfunction "E_E") (pintype "passive"))
      (node (ref "U$44") (pin "P$1") (pinfunction "A_P$1") (pintype "bidirectional"))
      (node (ref "U$45") (pin "+") (pinfunction "+_+") (pintype "passive"))
      (node (ref "U$46") (pin "1") (pinfunction "1_1") (pintype "passive"))
    )
    (net (code "31") (name "Net-(U$47-2)") (class "Default")
      (node (ref "U$45") (pin "-") (pinfunction "-_-") (pintype "passive"))
      (node (ref "U$46") (pin "2") (pinfunction "2_2") (pintype "passive"))
      (node (ref "U$47") (pin "P$2") (pinfunction "2_P$2") (pintype "passive"))
      (node (ref "U$48") (pin "P$1") (pinfunction "1_P$1") (pintype "passive"))
    )
    (net (code "32") (name "Net-(U$48-2)") (class "Default")
      (node (ref "U$48") (pin "P$2") (pinfunction "2_P$2") (pintype "passive"))
      (node (ref "U$97") (pin "1C") (pinfunction "C_1C") (pintype "passive"))
    )
    (net (code "33") (name "Net-(U$54-1)") (class "Default")
      (node (ref "U$53") (pin "2") (pinfunction "2_2") (pintype "passive"))
      (node (ref "U$54") (pin "P$1") (pinfunction "1_P$1") (pintype "passive"))
    )
    (net (code "34") (name "Net-(U$54-2)") (class "Default")
      (node (ref "U$54") (pin "P$2") (pinfunction "2_P$2") (pintype "passive"))
      (node (ref "U$56") (pin "C/G") (pinfunction "G_C/G") (pintype "passive"))
      (node (ref "U$57") (pin "C/G") (pinfunction "G_C/G") (pintype "passive"))
    )
    (net (code "35") (name "Net-(U$55-B)") (class "Default")
      (node (ref "U$55") (pin "B/S") (pinfunction "B_B/S") (pintype "passive"))
      (node (ref "U$77") (pin "P$2") (pinfunction "2_P$2") (pintype "passive"))
      (node (ref "U$80") (pin "P$1") (pinfunction "1_P$1") (pintype "passive"))
    )
    (net (code "36") (name "Net-(U$55-C)") (class "Default")
      (node (ref "U$55") (pin "C/G") (pinfunction "C_C/G") (pintype "passive"))
      (node (ref "U$56") (pin "B/S") (pinfunction "S_B/S") (pintype "passive"))
      (node (ref "U$57") (pin "B/S") (pinfunction "S_B/S") (pintype "passive"))
      (node (ref "U$58") (pin "B/S") (pinfunction "S_B/S") (pintype "passive"))
      (node (ref "U$59") (pin "B/S") (pinfunction "S_B/S") (pintype "passive"))
    )
    (net (code "37") (name "Net-(U$55-E)") (class "Default")
      (node (ref "U$55") (pin "E/D") (pinfunction "E_E/D") (pintype "passive"))
      (node (ref "U$62") (pin "P$2") (pinfunction "2_P$2") (pintype "passive"))
    )
    (net (code "38") (name "Net-(U$56-D)") (class "Default")
      (node (ref "U$56") (pin "E/D") (pinfunction "D_E/D") (pintype "passive"))
      (node (ref "U$57") (pin "E/D") (pinfunction "D_E/D") (pintype "passive"))
      (node (ref "U$61") (pin "B/S") (pinfunction "B_B/S") (pintype "passive"))
      (node (ref "U$82") (pin "P$1") (pinfunction "1_P$1") (pintype "passive"))
    )
    (net (code "39") (name "Net-(U$58-D)") (class "Default")
      (node (ref "U$58") (pin "E/D") (pinfunction "D_E/D") (pintype "passive"))
      (node (ref "U$59") (pin "E/D") (pinfunction "D_E/D") (pintype "passive"))
      (node (ref "U$70") (pin "B/S") (pinfunction "B_B/S") (pintype "passive"))
      (node (ref "U$81") (pin "P$1") (pinfunction "1_P$1") (pintype "passive"))
    )
    (net (code "40") (name "Net-(U$58-G)") (class "Default")
      (node (ref "U$58") (pin "C/G") (pinfunction "G_C/G") (pintype "passive"))
      (node (ref "U$59") (pin "C/G") (pinfunction "G_C/G") (pintype "passive"))
      (node (ref "U$60") (pin "P$2") (pinfunction "2_P$2") (pintype "passive"))
    )
    (net (code "41") (name "Net-(U$60-1)") (class "Default")
      (node (ref "U$52") (pin "2") (pinfunction "2_2") (pintype "passive"))
      (node (ref "U$60") (pin "P$1") (pinfunction "1_P$1") (pintype "passive"))
    )
    (net (code "42") (name "Net-(U$61-E)") (class "Default")
      (node (ref "U$61") (pin "E/D") (pinfunction "E_E/D") (pintype "passive"))
      (node (ref "U$64") (pin "B") (pinfunction "B_B") (pintype "passive"))
      (node (ref "U$79") (pin "P$2") (pinfunction "2_P$2") (pintype "passive"))
    )
    (net (code "43") (name "Net-(U$62-1)") (class "Default")
      (node (ref "U$62") (pin "P$1") (pinfunction "1_P$1") (pintype "passive"))
      (node (ref "U$63") (pin "1") (pinfunction "1_1") (pintype "passive"))
      (node (ref "U$63") (pin "2") (pinfunction "2_2") (pintype "passive"))
    )
    (net (code "44") (name "Net-(U$65-A)") (class "Default")
      (node (ref "U$64") (pin "E") (pinfunction "E_E") (pintype "passive"))
      (node (ref "U$65") (pin "P$1") (pinfunction "A_P$1") (pintype "bidirectional"))
      (node (ref "U$66") (pin "+") (pinfunction "+_+") (pintype "passive"))
      (node (ref "U$67") (pin "1") (pinfunction "1_1") (pintype "passive"))
    )
    (net (code "45") (name "Net-(U$68-2)") (class "Default")
      (node (ref "U$66") (pin "-") (pinfunction "-_-") (pintype "passive"))
      (node (ref "U$67") (pin "2") (pinfunction "2_2") (pintype "passive"))
      (node (ref "U$68") (pin "P$2") (pinfunction "2_P$2") (pintype "passive"))
      (node (ref "U$69") (pin "P$1") (pinfunction "1_P$1") (pintype "passive"))
    )
    (net (code "46") (name "Net-(U$69-2)") (class "Default")
      (node (ref "U$69") (pin "P$2") (pinfunction "2_P$2") (pintype "passive"))
      (node (ref "U$98") (pin "2C") (pinfunction "C_2C") (pintype "passive"))
    )
    (net (code "47") (name "Net-(U$70-E)") (class "Default")
      (node (ref "U$70") (pin "E/D") (pinfunction "E_E/D") (pintype "passive"))
      (node (ref "U$71") (pin "B") (pinfunction "B_B") (pintype "passive"))
      (node (ref "U$78") (pin "P$2") (pinfunction "2_P$2") (pintype "passive"))
    )
    (net (code "48") (name "Net-(U$72-A)") (class "Default")
      (node (ref "U$71") (pin "E") (pinfunction "E_E") (pintype "passive"))
      (node (ref "U$72") (pin "P$1") (pinfunction "A_P$1") (pintype "bidirectional"))
      (node (ref "U$73") (pin "+") (pinfunction "+_+") (pintype "passive"))
      (node (ref "U$74") (pin "1") (pinfunction "1_1") (pintype "passive"))
    )
    (net (code "49") (name "Net-(U$75-2)") (class "Default")
      (node (ref "U$73") (pin "-") (pinfunction "-_-") (pintype "passive"))
      (node (ref "U$74") (pin "2") (pinfunction "2_2") (pintype "passive"))
      (node (ref "U$75") (pin "P$2") (pinfunction "2_P$2") (pintype "passive"))
      (node (ref "U$76") (pin "P$1") (pinfunction "1_P$1") (pintype "passive"))
    )
    (net (code "50") (name "Net-(U$76-2)") (class "Default")
      (node (ref "U$76") (pin "P$2") (pinfunction "2_P$2") (pintype "passive"))
      (node (ref "U$98") (pin "1C") (pinfunction "C_1C") (pintype "passive"))
    )
    (net (code "51") (name "Net-(U$93-1)") (class "Default")
      (node (ref "U$85") (pin "+") (pinfunction "+_+") (pintype "passive"))
      (node (ref "U$88") (pin "B") (pinfunction "B_B") (pintype "passive"))
      (node (ref "U$93") (pin "P$1") (pinfunction "1_P$1") (pintype "passive"))
    )
    (net (code "52") (name "Net-(U$94-B)") (class "Default")
      (node (ref "U$94") (pin "P$2") (pinfunction "B_P$2") (pintype "bidirectional"))
      (node (ref "U$95") (pin "P$2") (pinfunction "2_P$2") (pintype "passive"))
    )
    (net (code "53") (name "Net-(U$96-1)") (class "Default")
      (node (ref "U$86") (pin "-") (pinfunction "-_-") (pintype "passive"))
      (node (ref "U$87") (pin "B") (pinfunction "B_B") (pintype "passive"))
      (node (ref "U$96") (pin "P$1") (pinfunction "1_P$1") (pintype "passive"))
    )
    (net (code "54") (name "Net-(U$100-1)") (class "Default")
      (node (ref "U$100") (pin "P$1") (pinfunction "1_P$1") (pintype "passive"))
      (node (ref "U$103") (pin "P$2") (pinfunction "B_P$2") (pintype "bidirectional"))
    )
    (net (code "55") (name "Net-(U$104-A)") (class "Default")
      (node (ref "U$104") (pin "P$1") (pinfunction "A_P$1") (pintype "bidirectional"))
      (node (ref "U$97") (pin "1NO") (pinfunction "NO_1NO") (pintype "passive"))
    )
    (net (code "56") (name "Net-(U$104-B)") (class "Default")
      (node (ref "U$104") (pin "P$2") (pinfunction "B_P$2") (pintype "bidirectional"))
      (node (ref "U$97") (pin "2NO") (pinfunction "NO_2NO") (pintype "passive"))
    )
    (net (code "57") (name "Net-(U$105-A)") (class "Default")
      (node (ref "U$105") (pin "P$1") (pinfunction "A_P$1") (pintype "bidirectional"))
      (node (ref "U$98") (pin "1NO") (pinfunction "NO_1NO") (pintype "passive"))
    )
    (net (code "58") (name "Net-(U$105-B)") (class "Default")
      (node (ref "U$105") (pin "P$2") (pinfunction "B_P$2") (pintype "bidirectional"))
      (node (ref "U$98") (pin "2NO") (pinfunction "NO_2NO") (pintype "passive"))
    )
    (net (code "59") (name "R+I") (class "Default")
      (node (ref "U$2") (pin "R+") (pinfunction "R+_R+") (pintype "bidirectional"))
      (node (ref "U$52") (pin "3") (pinfunction "3_3") (pintype "passive"))
    )
    (net (code "60") (name "R+VCC") (class "Default")
      (node (ref "R6") (pin "2") (pinfunction "2_2") (pintype "passive"))
      (node (ref "U$61") (pin "C/G") (pinfunction "C_C/G") (pintype "passive"))
      (node (ref "U$64") (pin "C") (pinfunction "C_C") (pintype "passive"))
      (node (ref "U$70") (pin "C/G") (pinfunction "C_C/G") (pintype "passive"))
      (node (ref "U$71") (pin "C") (pinfunction "C_C") (pintype "passive"))
      (node (ref "U$80") (pin "P$2") (pinfunction "2_P$2") (pintype "passive"))
      (node (ref "U$81") (pin "P$2") (pinfunction "2_P$2") (pintype "passive"))
      (node (ref "U$82") (pin "P$2") (pinfunction "2_P$2") (pintype "passive"))
      (node (ref "U$83") (pin "+") (pinfunction "+_+") (pintype "passive"))
      (node (ref "U$88") (pin "E") (pinfunction "E_E") (pintype "passive"))
      (node (ref "U$89") (pin "A") (pinfunction "A_A") (pintype "passive"))
      (node (ref "U$95") (pin "P$1") (pinfunction "1_P$1") (pintype "passive"))
    )
    (net (code "61") (name "R-I") (class "Default")
      (node (ref "U$2") (pin "R-") (pinfunction "R-_R-") (pintype "bidirectional"))
      (node (ref "U$53") (pin "3") (pinfunction "3_3") (pintype "passive"))
    )
    (net (code "62") (name "R-VCC") (class "Default")
      (node (ref "R8") (pin "1") (pinfunction "1_1") (pintype "passive"))
      (node (ref "U$10") (pin "-") (pinfunction "-_-") (pintype "passive"))
      (node (ref "U$63") (pin "3") (pinfunction "3_3") (pintype "passive"))
      (node (ref "U$65") (pin "P$2") (pinfunction "B_P$2") (pintype "bidirectional"))
      (node (ref "U$72") (pin "P$2") (pinfunction "B_P$2") (pintype "bidirectional"))
      (node (ref "U$77") (pin "P$1") (pinfunction "1_P$1") (pintype "passive"))
      (node (ref "U$78") (pin "P$1") (pinfunction "1_P$1") (pintype "passive"))
      (node (ref "U$79") (pin "P$1") (pinfunction "1_P$1") (pintype "passive"))
      (node (ref "U$87") (pin "E") (pinfunction "E_E") (pintype "passive"))
      (node (ref "U$90") (pin "C") (pinfunction "C_C") (pintype "passive"))
    )
    (net (code "63") (name "unconnected-(U$97B-NC-Pad1NC)") (class "Default")
      (node (ref "U$97") (pin "1NC") (pinfunction "NC_1NC") (pintype "passive"))
    )
    (net (code "64") (name "unconnected-(U$97C-NC-Pad2NC)") (class "Default")
      (node (ref "U$97") (pin "2NC") (pinfunction "NC_2NC") (pintype "passive"))
    )
    (net (code "65") (name "unconnected-(U$98B-NC-Pad1NC)") (class "Default")
      (node (ref "U$98") (pin "1NC") (pinfunction "NC_1NC") (pintype "passive"))
    )
    (net (code "66") (name "unconnected-(U$98C-NC-Pad2NC)") (class "Default")
      (node (ref "U$98") (pin "2NC") (pinfunction "NC_2NC") (pintype "passive"))
    )
    (net (code "67") (name "unconnected-(U$101-PadP$1)") (class "Default")
      (node (ref "U$101") (pin "P$1") (pinfunction "P$1_P$1") (pintype "bidirectional"))
    )
    (net (code "68") (name "unconnected-(U$102-PadP$1)") (class "Default")
      (node (ref "U$102") (pin "P$1") (pinfunction "P$1_P$1") (pintype "bidirectional"))
    )
    (net (code "69") (name "unconnected-(U$106-PadP$1)") (class "Default")
      (node (ref "U$106") (pin "P$1") (pinfunction "P$1_P$1") (pintype "bidirectional"))
    )
    (net (code "70") (name "unconnected-(U$107-PadP$1)") (class "Default")
      (node (ref "U$107") (pin "P$1") (pinfunction "P$1_P$1") (pintype "bidirectional"))
    )
  )
)
